# unit-shield.net
KiCad netlist of a schematic drawn in EAGLE
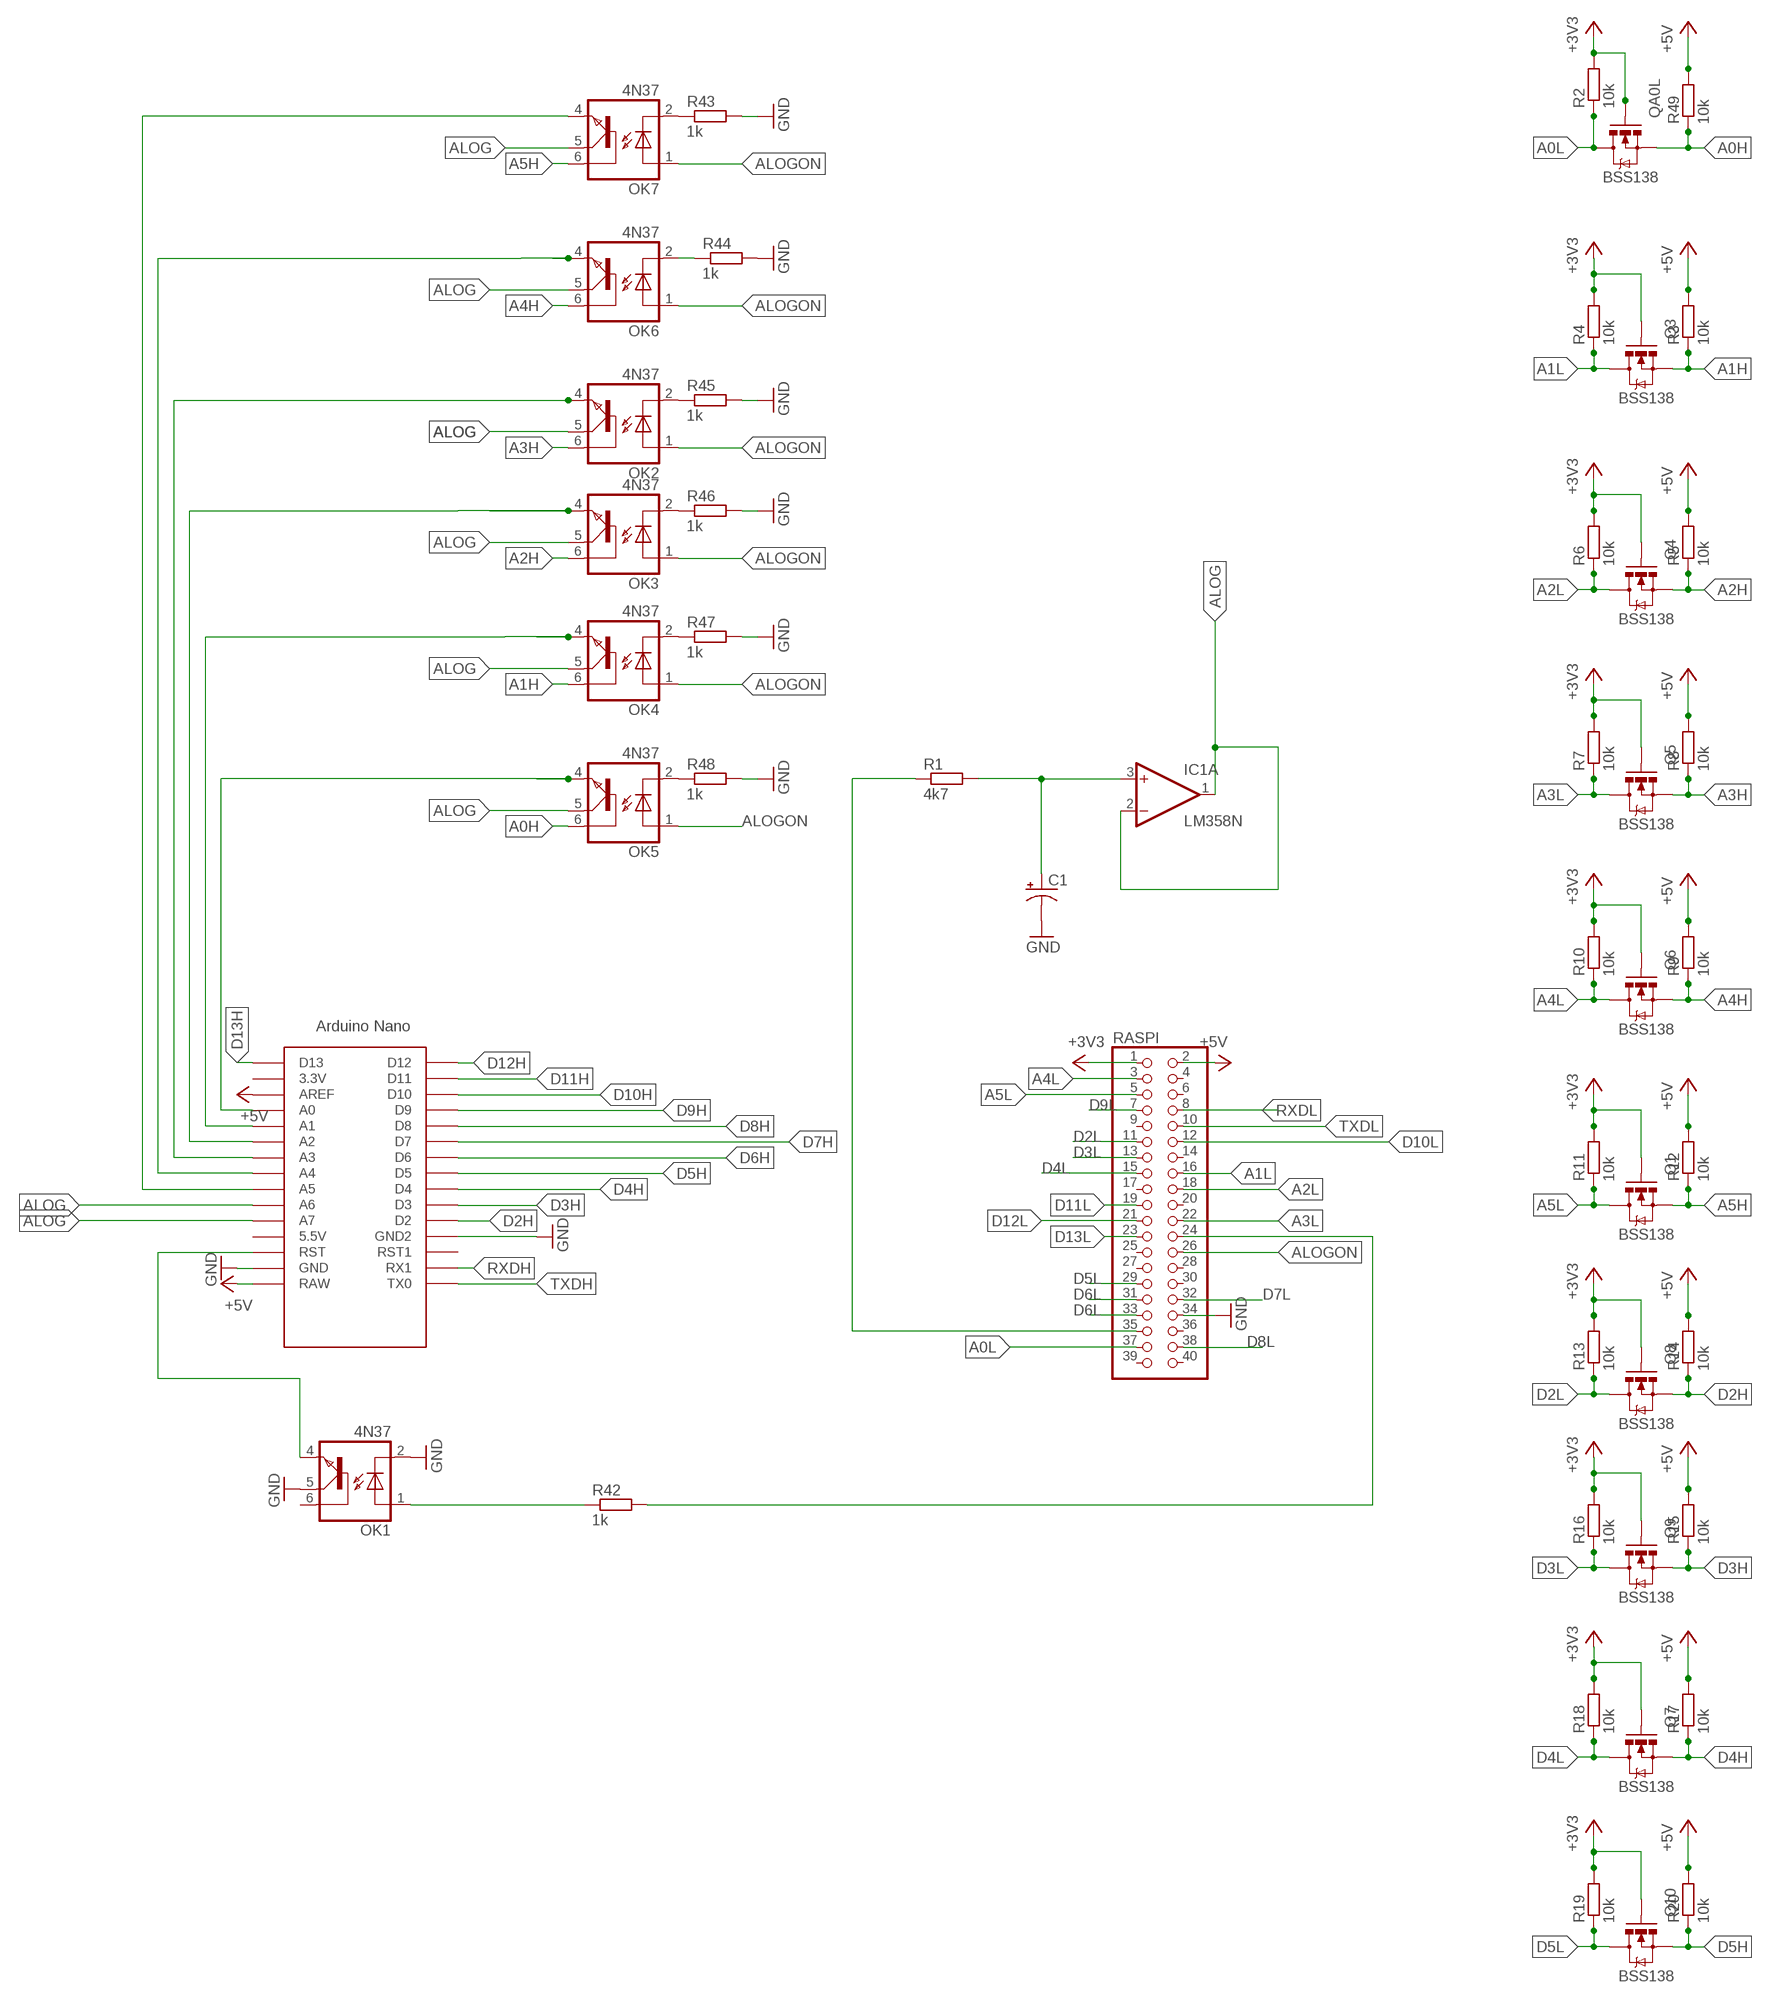
[diagram p0: schematic, sheet 1, part 1 of 2]
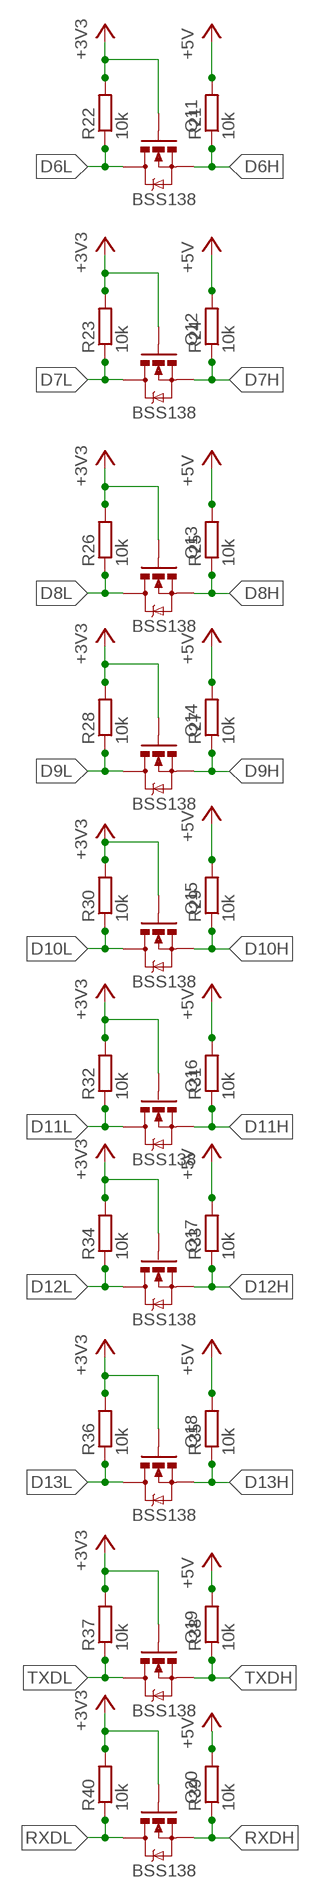
[diagram p1: schematic, sheet 1, part 2 of 2]

(export (version "E")
  (design (tool "Eeschema 10.0.6"))
  (components
    (comp (ref "C1")
      (value "CPOL-USB")
      (footprint "eagle-import:PANASONIC_B")
      (libsource (lib "eagle-import") (part "CPOL-USB"))
    )
    (comp (ref "IC1")
      (value "LM358N")
      (footprint "eagle-import:DIL08")
      (libsource (lib "eagle-import") (part "LM358N"))
    )
    (comp (ref "OK1")
      (value "4N37")
      (footprint "eagle-import:DIL06")
      (fields (field (name "MF") "FAIRCHILD SEMICONDUCTOR"))
      (libsource (lib "eagle-import") (part "4N37"))
    )
    (comp (ref "OK2")
      (value "4N37")
      (footprint "eagle-import:DIL06")
      (fields (field (name "MF") "FAIRCHILD SEMICONDUCTOR"))
      (libsource (lib "eagle-import") (part "4N37"))
    )
    (comp (ref "OK3")
      (value "4N37")
      (footprint "eagle-import:DIL06")
      (fields (field (name "MF") "FAIRCHILD SEMICONDUCTOR"))
      (libsource (lib "eagle-import") (part "4N37"))
    )
    (comp (ref "OK4")
      (value "4N37")
      (footprint "eagle-import:DIL06")
      (fields (field (name "MF") "FAIRCHILD SEMICONDUCTOR"))
      (libsource (lib "eagle-import") (part "4N37"))
    )
    (comp (ref "OK5")
      (value "4N37")
      (footprint "eagle-import:DIL06")
      (fields (field (name "MF") "FAIRCHILD SEMICONDUCTOR"))
      (libsource (lib "eagle-import") (part "4N37"))
    )
    (comp (ref "OK6")
      (value "4N37")
      (footprint "eagle-import:DIL06")
      (fields (field (name "MF") "FAIRCHILD SEMICONDUCTOR"))
      (libsource (lib "eagle-import") (part "4N37"))
    )
    (comp (ref "OK7")
      (value "4N37")
      (footprint "eagle-import:DIL06")
      (fields (field (name "MF") "FAIRCHILD SEMICONDUCTOR"))
      (libsource (lib "eagle-import") (part "4N37"))
    )
    (comp (ref "Q1")
      (value "BSS138")
      (footprint "eagle-import:SOT23-3")
      (libsource (lib "eagle-import") (part "MOSFET-NCHANNELSMD"))
    )
    (comp (ref "Q3")
      (value "BSS138")
      (footprint "eagle-import:SOT23-3")
      (libsource (lib "eagle-import") (part "MOSFET-NCHANNELSMD"))
    )
    (comp (ref "Q4")
      (value "BSS138")
      (footprint "eagle-import:SOT23-3")
      (libsource (lib "eagle-import") (part "MOSFET-NCHANNELSMD"))
    )
    (comp (ref "Q5")
      (value "BSS138")
      (footprint "eagle-import:SOT23-3")
      (libsource (lib "eagle-import") (part "MOSFET-NCHANNELSMD"))
    )
    (comp (ref "Q6")
      (value "BSS138")
      (footprint "eagle-import:SOT23-3")
      (libsource (lib "eagle-import") (part "MOSFET-NCHANNELSMD"))
    )
    (comp (ref "Q7")
      (value "BSS138")
      (footprint "eagle-import:SOT23-3")
      (libsource (lib "eagle-import") (part "MOSFET-NCHANNELSMD"))
    )
    (comp (ref "Q8")
      (value "BSS138")
      (footprint "eagle-import:SOT23-3")
      (libsource (lib "eagle-import") (part "MOSFET-NCHANNELSMD"))
    )
    (comp (ref "Q9")
      (value "BSS138")
      (footprint "eagle-import:SOT23-3")
      (libsource (lib "eagle-import") (part "MOSFET-NCHANNELSMD"))
    )
    (comp (ref "Q10")
      (value "BSS138")
      (footprint "eagle-import:SOT23-3")
      (libsource (lib "eagle-import") (part "MOSFET-NCHANNELSMD"))
    )
    (comp (ref "Q11")
      (value "BSS138")
      (footprint "eagle-import:SOT23-3")
      (libsource (lib "eagle-import") (part "MOSFET-NCHANNELSMD"))
    )
    (comp (ref "Q12")
      (value "BSS138")
      (footprint "eagle-import:SOT23-3")
      (libsource (lib "eagle-import") (part "MOSFET-NCHANNELSMD"))
    )
    (comp (ref "Q13")
      (value "BSS138")
      (footprint "eagle-import:SOT23-3")
      (libsource (lib "eagle-import") (part "MOSFET-NCHANNELSMD"))
    )
    (comp (ref "Q14")
      (value "BSS138")
      (footprint "eagle-import:SOT23-3")
      (libsource (lib "eagle-import") (part "MOSFET-NCHANNELSMD"))
    )
    (comp (ref "Q15")
      (value "BSS138")
      (footprint "eagle-import:SOT23-3")
      (libsource (lib "eagle-import") (part "MOSFET-NCHANNELSMD"))
    )
    (comp (ref "Q16")
      (value "BSS138")
      (footprint "eagle-import:SOT23-3")
      (libsource (lib "eagle-import") (part "MOSFET-NCHANNELSMD"))
    )
    (comp (ref "Q17")
      (value "BSS138")
      (footprint "eagle-import:SOT23-3")
      (libsource (lib "eagle-import") (part "MOSFET-NCHANNELSMD"))
    )
    (comp (ref "Q18")
      (value "BSS138")
      (footprint "eagle-import:SOT23-3")
      (libsource (lib "eagle-import") (part "MOSFET-NCHANNELSMD"))
    )
    (comp (ref "Q19")
      (value "BSS138")
      (footprint "eagle-import:SOT23-3")
      (libsource (lib "eagle-import") (part "MOSFET-NCHANNELSMD"))
    )
    (comp (ref "Q20")
      (value "BSS138")
      (footprint "eagle-import:SOT23-3")
      (libsource (lib "eagle-import") (part "MOSFET-NCHANNELSMD"))
    )
    (comp (ref "QA0L")
      (value "BSS138")
      (footprint "eagle-import:SOT23-3")
      (libsource (lib "eagle-import") (part "MOSFET-NCHANNELSMD"))
    )
    (comp (ref "R1")
      (value "4k7")
      (footprint "eagle-import:M3216")
      (libsource (lib "eagle-import") (part "R-EU_M3216"))
    )
    (comp (ref "R2")
      (value "10k")
      (footprint "eagle-import:M3216")
      (libsource (lib "eagle-import") (part "R-EU_M3216"))
    )
    (comp (ref "R3")
      (value "10k")
      (footprint "eagle-import:M3216")
      (libsource (lib "eagle-import") (part "R-EU_M3216"))
    )
    (comp (ref "R4")
      (value "10k")
      (footprint "eagle-import:M3216")
      (libsource (lib "eagle-import") (part "R-EU_M3216"))
    )
    (comp (ref "R5")
      (value "10k")
      (footprint "eagle-import:M3216")
      (libsource (lib "eagle-import") (part "R-EU_M3216"))
    )
    (comp (ref "R6")
      (value "10k")
      (footprint "eagle-import:M3216")
      (libsource (lib "eagle-import") (part "R-EU_M3216"))
    )
    (comp (ref "R7")
      (value "10k")
      (footprint "eagle-import:M3216")
      (libsource (lib "eagle-import") (part "R-EU_M3216"))
    )
    (comp (ref "R8")
      (value "10k")
      (footprint "eagle-import:M3216")
      (libsource (lib "eagle-import") (part "R-EU_M3216"))
    )
    (comp (ref "R9")
      (value "10k")
      (footprint "eagle-import:M3216")
      (libsource (lib "eagle-import") (part "R-EU_M3216"))
    )
    (comp (ref "R10")
      (value "10k")
      (footprint "eagle-import:M3216")
      (libsource (lib "eagle-import") (part "R-EU_M3216"))
    )
    (comp (ref "R11")
      (value "10k")
      (footprint "eagle-import:M3216")
      (libsource (lib "eagle-import") (part "R-EU_M3216"))
    )
    (comp (ref "R12")
      (value "10k")
      (footprint "eagle-import:M3216")
      (libsource (lib "eagle-import") (part "R-EU_M3216"))
    )
    (comp (ref "R13")
      (value "10k")
      (footprint "eagle-import:M3216")
      (libsource (lib "eagle-import") (part "R-EU_M3216"))
    )
    (comp (ref "R14")
      (value "10k")
      (footprint "eagle-import:M3216")
      (libsource (lib "eagle-import") (part "R-EU_M3216"))
    )
    (comp (ref "R15")
      (value "10k")
      (footprint "eagle-import:M3216")
      (libsource (lib "eagle-import") (part "R-EU_M3216"))
    )
    (comp (ref "R16")
      (value "10k")
      (footprint "eagle-import:M3216")
      (libsource (lib "eagle-import") (part "R-EU_M3216"))
    )
    (comp (ref "R17")
      (value "10k")
      (footprint "eagle-import:M3216")
      (libsource (lib "eagle-import") (part "R-EU_M3216"))
    )
    (comp (ref "R18")
      (value "10k")
      (footprint "eagle-import:M3216")
      (libsource (lib "eagle-import") (part "R-EU_M3216"))
    )
    (comp (ref "R19")
      (value "10k")
      (footprint "eagle-import:M3216")
      (libsource (lib "eagle-import") (part "R-EU_M3216"))
    )
    (comp (ref "R20")
      (value "10k")
      (footprint "eagle-import:M3216")
      (libsource (lib "eagle-import") (part "R-EU_M3216"))
    )
    (comp (ref "R21")
      (value "10k")
      (footprint "eagle-import:M3216")
      (libsource (lib "eagle-import") (part "R-EU_M3216"))
    )
    (comp (ref "R22")
      (value "10k")
      (footprint "eagle-import:M3216")
      (libsource (lib "eagle-import") (part "R-EU_M3216"))
    )
    (comp (ref "R23")
      (value "10k")
      (footprint "eagle-import:M3216")
      (libsource (lib "eagle-import") (part "R-EU_M3216"))
    )
    (comp (ref "R24")
      (value "10k")
      (footprint "eagle-import:M3216")
      (libsource (lib "eagle-import") (part "R-EU_M3216"))
    )
    (comp (ref "R25")
      (value "10k")
      (footprint "eagle-import:M3216")
      (libsource (lib "eagle-import") (part "R-EU_M3216"))
    )
    (comp (ref "R26")
      (value "10k")
      (footprint "eagle-import:M3216")
      (libsource (lib "eagle-import") (part "R-EU_M3216"))
    )
    (comp (ref "R27")
      (value "10k")
      (footprint "eagle-import:M3216")
      (libsource (lib "eagle-import") (part "R-EU_M3216"))
    )
    (comp (ref "R28")
      (value "10k")
      (footprint "eagle-import:M3216")
      (libsource (lib "eagle-import") (part "R-EU_M3216"))
    )
    (comp (ref "R29")
      (value "10k")
      (footprint "eagle-import:M3216")
      (libsource (lib "eagle-import") (part "R-EU_M3216"))
    )
    (comp (ref "R30")
      (value "10k")
      (footprint "eagle-import:M3216")
      (libsource (lib "eagle-import") (part "R-EU_M3216"))
    )
    (comp (ref "R31")
      (value "10k")
      (footprint "eagle-import:M3216")
      (libsource (lib "eagle-import") (part "R-EU_M3216"))
    )
    (comp (ref "R32")
      (value "10k")
      (footprint "eagle-import:M3216")
      (libsource (lib "eagle-import") (part "R-EU_M3216"))
    )
    (comp (ref "R33")
      (value "10k")
      (footprint "eagle-import:M3216")
      (libsource (lib "eagle-import") (part "R-EU_M3216"))
    )
    (comp (ref "R34")
      (value "10k")
      (footprint "eagle-import:M3216")
      (libsource (lib "eagle-import") (part "R-EU_M3216"))
    )
    (comp (ref "R35")
      (value "10k")
      (footprint "eagle-import:M3216")
      (libsource (lib "eagle-import") (part "R-EU_M3216"))
    )
    (comp (ref "R36")
      (value "10k")
      (footprint "eagle-import:M3216")
      (libsource (lib "eagle-import") (part "R-EU_M3216"))
    )
    (comp (ref "R37")
      (value "10k")
      (footprint "eagle-import:M3216")
      (libsource (lib "eagle-import") (part "R-EU_M3216"))
    )
    (comp (ref "R38")
      (value "10k")
      (footprint "eagle-import:M3216")
      (libsource (lib "eagle-import") (part "R-EU_M3216"))
    )
    (comp (ref "R39")
      (value "10k")
      (footprint "eagle-import:M3216")
      (libsource (lib "eagle-import") (part "R-EU_M3216"))
    )
    (comp (ref "R40")
      (value "10k")
      (footprint "eagle-import:M3216")
      (libsource (lib "eagle-import") (part "R-EU_M3216"))
    )
    (comp (ref "R42")
      (value "1k")
      (footprint "eagle-import:M3216")
      (libsource (lib "eagle-import") (part "R-EU_M3216"))
    )
    (comp (ref "R43")
      (value "1k")
      (footprint "eagle-import:M3216")
      (libsource (lib "eagle-import") (part "R-EU_M3216"))
    )
    (comp (ref "R44")
      (value "1k")
      (footprint "eagle-import:M3216")
      (libsource (lib "eagle-import") (part "R-EU_M3216"))
    )
    (comp (ref "R45")
      (value "1k")
      (footprint "eagle-import:M3216")
      (libsource (lib "eagle-import") (part "R-EU_M3216"))
    )
    (comp (ref "R46")
      (value "1k")
      (footprint "eagle-import:M3216")
      (libsource (lib "eagle-import") (part "R-EU_M3216"))
    )
    (comp (ref "R47")
      (value "1k")
      (footprint "eagle-import:M3216")
      (libsource (lib "eagle-import") (part "R-EU_M3216"))
    )
    (comp (ref "R48")
      (value "1k")
      (footprint "eagle-import:M3216")
      (libsource (lib "eagle-import") (part "R-EU_M3216"))
    )
    (comp (ref "R49")
      (value "10k")
      (footprint "eagle-import:M3216")
      (libsource (lib "eagle-import") (part "R-EU_M3216"))
    )
    (comp (ref "RASPI")
      (value "PINHD-2X20")
      (footprint "eagle-import:2X20")
      (libsource (lib "eagle-import") (part "PINHD-2X20"))
    )
    (comp (ref "U$1")
      (value "NANO")
      (footprint "eagle-import:NANO")
      (libsource (lib "eagle-import") (part "NANO"))
    )
  )
  (nets
    (net (code "1") (name "+3V3") (class "Default")
      (node (ref "Q1") (pin "1") (pinfunction "G_1") (pintype "passive"))
      (node (ref "Q10") (pin "1") (pinfunction "G_1") (pintype "passive"))
      (node (ref "Q11") (pin "1") (pinfunction "G_1") (pintype "passive"))
      (node (ref "Q12") (pin "1") (pinfunction "G_1") (pintype "passive"))
      (node (ref "Q13") (pin "1") (pinfunction "G_1") (pintype "passive"))
      (node (ref "Q14") (pin "1") (pinfunction "G_1") (pintype "passive"))
      (node (ref "Q15") (pin "1") (pinfunction "G_1") (pintype "passive"))
      (node (ref "Q16") (pin "1") (pinfunction "G_1") (pintype "passive"))
      (node (ref "Q17") (pin "1") (pinfunction "G_1") (pintype "passive"))
      (node (ref "Q18") (pin "1") (pinfunction "G_1") (pintype "passive"))
      (node (ref "Q19") (pin "1") (pinfunction "G_1") (pintype "passive"))
      (node (ref "Q20") (pin "1") (pinfunction "G_1") (pintype "passive"))
      (node (ref "Q3") (pin "1") (pinfunction "G_1") (pintype "passive"))
      (node (ref "Q4") (pin "1") (pinfunction "G_1") (pintype "passive"))
      (node (ref "Q5") (pin "1") (pinfunction "G_1") (pintype "passive"))
      (node (ref "Q6") (pin "1") (pinfunction "G_1") (pintype "passive"))
      (node (ref "Q7") (pin "1") (pinfunction "G_1") (pintype "passive"))
      (node (ref "Q8") (pin "1") (pinfunction "G_1") (pintype "passive"))
      (node (ref "Q9") (pin "1") (pinfunction "G_1") (pintype "passive"))
      (node (ref "QA0L") (pin "1") (pinfunction "G_1") (pintype "passive"))
      (node (ref "R10") (pin "2") (pinfunction "2_2") (pintype "passive"))
      (node (ref "R11") (pin "2") (pinfunction "2_2") (pintype "passive"))
      (node (ref "R13") (pin "2") (pinfunction "2_2") (pintype "passive"))
      (node (ref "R16") (pin "2") (pinfunction "2_2") (pintype "passive"))
      (node (ref "R18") (pin "2") (pinfunction "2_2") (pintype "passive"))
      (node (ref "R19") (pin "2") (pinfunction "2_2") (pintype "passive"))
      (node (ref "R2") (pin "2") (pinfunction "2_2") (pintype "passive"))
      (node (ref "R22") (pin "2") (pinfunction "2_2") (pintype "passive"))
      (node (ref "R23") (pin "2") (pinfunction "2_2") (pintype "passive"))
      (node (ref "R26") (pin "2") (pinfunction "2_2") (pintype "passive"))
      (node (ref "R28") (pin "2") (pinfunction "2_2") (pintype "passive"))
      (node (ref "R30") (pin "2") (pinfunction "2_2") (pintype "passive"))
      (node (ref "R32") (pin "2") (pinfunction "2_2") (pintype "passive"))
      (node (ref "R34") (pin "2") (pinfunction "2_2") (pintype "passive"))
      (node (ref "R36") (pin "2") (pinfunction "2_2") (pintype "passive"))
      (node (ref "R37") (pin "2") (pinfunction "2_2") (pintype "passive"))
      (node (ref "R4") (pin "2") (pinfunction "2_2") (pintype "passive"))
      (node (ref "R40") (pin "2") (pinfunction "2_2") (pintype "passive"))
      (node (ref "R6") (pin "2") (pinfunction "2_2") (pintype "passive"))
      (node (ref "R7") (pin "2") (pinfunction "2_2") (pintype "passive"))
      (node (ref "RASPI") (pin "1") (pinfunction "1_1") (pintype "passive"))
    )
    (net (code "2") (name "+5V") (class "Default")
      (node (ref "R12") (pin "2") (pinfunction "2_2") (pintype "passive"))
      (node (ref "R14") (pin "2") (pinfunction "2_2") (pintype "passive"))
      (node (ref "R15") (pin "2") (pinfunction "2_2") (pintype "passive"))
      (node (ref "R17") (pin "2") (pinfunction "2_2") (pintype "passive"))
      (node (ref "R20") (pin "2") (pinfunction "2_2") (pintype "passive"))
      (node (ref "R21") (pin "2") (pinfunction "2_2") (pintype "passive"))
      (node (ref "R24") (pin "2") (pinfunction "2_2") (pintype "passive"))
      (node (ref "R25") (pin "2") (pinfunction "2_2") (pintype "passive"))
      (node (ref "R27") (pin "2") (pinfunction "2_2") (pintype "passive"))
      (node (ref "R29") (pin "2") (pinfunction "2_2") (pintype "passive"))
      (node (ref "R3") (pin "2") (pinfunction "2_2") (pintype "passive"))
      (node (ref "R31") (pin "2") (pinfunction "2_2") (pintype "passive"))
      (node (ref "R33") (pin "2") (pinfunction "2_2") (pintype "passive"))
      (node (ref "R35") (pin "2") (pinfunction "2_2") (pintype "passive"))
      (node (ref "R38") (pin "2") (pinfunction "2_2") (pintype "passive"))
      (node (ref "R39") (pin "2") (pinfunction "2_2") (pintype "passive"))
      (node (ref "R49") (pin "2") (pinfunction "2_2") (pintype "passive"))
      (node (ref "R5") (pin "2") (pinfunction "2_2") (pintype "passive"))
      (node (ref "R8") (pin "2") (pinfunction "2_2") (pintype "passive"))
      (node (ref "R9") (pin "2") (pinfunction "2_2") (pintype "passive"))
      (node (ref "RASPI") (pin "2") (pinfunction "2_2") (pintype "passive"))
      (node (ref "U$1") (pin "AREF") (pinfunction "AREF_AREF") (pintype "bidirectional"))
      (node (ref "U$1") (pin "RAW") (pinfunction "RAW_RAW") (pintype "bidirectional"))
    )
    (net (code "3") (name "A0H") (class "Default")
      (node (ref "OK5") (pin "6") (pinfunction "BAS_6") (pintype "passive"))
      (node (ref "QA0L") (pin "2") (pinfunction "S_2") (pintype "passive"))
      (node (ref "R49") (pin "1") (pinfunction "1_1") (pintype "passive"))
    )
    (net (code "4") (name "A0L") (class "Default")
      (node (ref "QA0L") (pin "3") (pinfunction "D_3") (pintype "passive"))
      (node (ref "R2") (pin "1") (pinfunction "1_1") (pintype "passive"))
      (node (ref "RASPI") (pin "37") (pinfunction "37_37") (pintype "passive"))
    )
    (net (code "5") (name "A1H") (class "Default")
      (node (ref "OK4") (pin "6") (pinfunction "BAS_6") (pintype "passive"))
      (node (ref "Q3") (pin "2") (pinfunction "S_2") (pintype "passive"))
      (node (ref "R3") (pin "1") (pinfunction "1_1") (pintype "passive"))
    )
    (net (code "6") (name "A1L") (class "Default")
      (node (ref "Q3") (pin "3") (pinfunction "D_3") (pintype "passive"))
      (node (ref "R4") (pin "1") (pinfunction "1_1") (pintype "passive"))
      (node (ref "RASPI") (pin "16") (pinfunction "16_16") (pintype "passive"))
    )
    (net (code "7") (name "A2H") (class "Default")
      (node (ref "OK3") (pin "6") (pinfunction "BAS_6") (pintype "passive"))
      (node (ref "Q4") (pin "2") (pinfunction "S_2") (pintype "passive"))
      (node (ref "R5") (pin "1") (pinfunction "1_1") (pintype "passive"))
    )
    (net (code "8") (name "A2L") (class "Default")
      (node (ref "Q4") (pin "3") (pinfunction "D_3") (pintype "passive"))
      (node (ref "R6") (pin "1") (pinfunction "1_1") (pintype "passive"))
      (node (ref "RASPI") (pin "18") (pinfunction "18_18") (pintype "passive"))
    )
    (net (code "9") (name "A3H") (class "Default")
      (node (ref "OK2") (pin "6") (pinfunction "BAS_6") (pintype "passive"))
      (node (ref "Q5") (pin "2") (pinfunction "S_2") (pintype "passive"))
      (node (ref "R8") (pin "1") (pinfunction "1_1") (pintype "passive"))
    )
    (net (code "10") (name "A3L") (class "Default")
      (node (ref "Q5") (pin "3") (pinfunction "D_3") (pintype "passive"))
      (node (ref "R7") (pin "1") (pinfunction "1_1") (pintype "passive"))
      (node (ref "RASPI") (pin "22") (pinfunction "22_22") (pintype "passive"))
    )
    (net (code "11") (name "A4H") (class "Default")
      (node (ref "OK6") (pin "6") (pinfunction "BAS_6") (pintype "passive"))
      (node (ref "Q6") (pin "2") (pinfunction "S_2") (pintype "passive"))
      (node (ref "R9") (pin "1") (pinfunction "1_1") (pintype "passive"))
    )
    (net (code "12") (name "A4L") (class "Default")
      (node (ref "Q6") (pin "3") (pinfunction "D_3") (pintype "passive"))
      (node (ref "R10") (pin "1") (pinfunction "1_1") (pintype "passive"))
      (node (ref "RASPI") (pin "3") (pinfunction "3_3") (pintype "passive"))
    )
    (net (code "13") (name "A5H") (class "Default")
      (node (ref "OK7") (pin "6") (pinfunction "BAS_6") (pintype "passive"))
      (node (ref "Q1") (pin "2") (pinfunction "S_2") (pintype "passive"))
      (node (ref "R12") (pin "1") (pinfunction "1_1") (pintype "passive"))
    )
    (net (code "14") (name "A5L") (class "Default")
      (node (ref "Q1") (pin "3") (pinfunction "D_3") (pintype "passive"))
      (node (ref "R11") (pin "1") (pinfunction "1_1") (pintype "passive"))
      (node (ref "RASPI") (pin "5") (pinfunction "5_5") (pintype "passive"))
    )
    (net (code "15") (name "ALOG") (class "Default")
      (node (ref "IC1") (pin "1") (pinfunction "OUT_1") (pintype "output"))
      (node (ref "IC1") (pin "2") (pinfunction "-IN_2") (pintype "input"))
      (node (ref "OK2") (pin "5") (pinfunction "COL_5") (pintype "passive"))
      (node (ref "OK3") (pin "5") (pinfunction "COL_5") (pintype "passive"))
      (node (ref "OK4") (pin "5") (pinfunction "COL_5") (pintype "passive"))
      (node (ref "OK5") (pin "5") (pinfunction "COL_5") (pintype "passive"))
      (node (ref "OK6") (pin "5") (pinfunction "COL_5") (pintype "passive"))
      (node (ref "OK7") (pin "5") (pinfunction "COL_5") (pintype "passive"))
      (node (ref "U$1") (pin "A6") (pinfunction "A6_A6") (pintype "bidirectional"))
      (node (ref "U$1") (pin "A7") (pinfunction "A7_A7") (pintype "bidirectional"))
    )
    (net (code "16") (name "ALOGON") (class "Default")
      (node (ref "OK2") (pin "1") (pinfunction "A_1") (pintype "passive"))
      (node (ref "OK3") (pin "1") (pinfunction "A_1") (pintype "passive"))
      (node (ref "OK4") (pin "1") (pinfunction "A_1") (pintype "passive"))
      (node (ref "OK5") (pin "1") (pinfunction "A_1") (pintype "passive"))
      (node (ref "OK6") (pin "1") (pinfunction "A_1") (pintype "passive"))
      (node (ref "OK7") (pin "1") (pinfunction "A_1") (pintype "passive"))
      (node (ref "RASPI") (pin "26") (pinfunction "26_26") (pintype "passive"))
    )
    (net (code "17") (name "D2H") (class "Default")
      (node (ref "Q8") (pin "2") (pinfunction "S_2") (pintype "passive"))
      (node (ref "R14") (pin "1") (pinfunction "1_1") (pintype "passive"))
      (node (ref "U$1") (pin "D2") (pinfunction "D2_D2") (pintype "bidirectional"))
    )
    (net (code "18") (name "D2L") (class "Default")
      (node (ref "Q8") (pin "3") (pinfunction "D_3") (pintype "passive"))
      (node (ref "R13") (pin "1") (pinfunction "1_1") (pintype "passive"))
      (node (ref "RASPI") (pin "11") (pinfunction "11_11") (pintype "passive"))
    )
    (net (code "19") (name "D3H") (class "Default")
      (node (ref "Q9") (pin "2") (pinfunction "S_2") (pintype "passive"))
      (node (ref "R15") (pin "1") (pinfunction "1_1") (pintype "passive"))
      (node (ref "U$1") (pin "D3") (pinfunction "D3_D3") (pintype "bidirectional"))
    )
    (net (code "20") (name "D3L") (class "Default")
      (node (ref "Q9") (pin "3") (pinfunction "D_3") (pintype "passive"))
      (node (ref "R16") (pin "1") (pinfunction "1_1") (pintype "passive"))
      (node (ref "RASPI") (pin "13") (pinfunction "13_13") (pintype "passive"))
    )
    (net (code "21") (name "D4H") (class "Default")
      (node (ref "Q7") (pin "2") (pinfunction "S_2") (pintype "passive"))
      (node (ref "R17") (pin "1") (pinfunction "1_1") (pintype "passive"))
      (node (ref "U$1") (pin "D4") (pinfunction "D4_D4") (pintype "bidirectional"))
    )
    (net (code "22") (name "D4L") (class "Default")
      (node (ref "Q7") (pin "3") (pinfunction "D_3") (pintype "passive"))
      (node (ref "R18") (pin "1") (pinfunction "1_1") (pintype "passive"))
      (node (ref "RASPI") (pin "15") (pinfunction "15_15") (pintype "passive"))
    )
    (net (code "23") (name "D5H") (class "Default")
      (node (ref "Q10") (pin "2") (pinfunction "S_2") (pintype "passive"))
      (node (ref "R20") (pin "1") (pinfunction "1_1") (pintype "passive"))
      (node (ref "U$1") (pin "D5") (pinfunction "D5_D5") (pintype "bidirectional"))
    )
    (net (code "24") (name "D5L") (class "Default")
      (node (ref "Q10") (pin "3") (pinfunction "D_3") (pintype "passive"))
      (node (ref "R19") (pin "1") (pinfunction "1_1") (pintype "passive"))
      (node (ref "RASPI") (pin "29") (pinfunction "29_29") (pintype "passive"))
    )
    (net (code "25") (name "D6H") (class "Default")
      (node (ref "Q11") (pin "2") (pinfunction "S_2") (pintype "passive"))
      (node (ref "R21") (pin "1") (pinfunction "1_1") (pintype "passive"))
      (node (ref "U$1") (pin "D6") (pinfunction "D6_D6") (pintype "bidirectional"))
    )
    (net (code "26") (name "D6L") (class "Default")
      (node (ref "Q11") (pin "3") (pinfunction "D_3") (pintype "passive"))
      (node (ref "R22") (pin "1") (pinfunction "1_1") (pintype "passive"))
      (node (ref "RASPI") (pin "31") (pinfunction "31_31") (pintype "passive"))
      (node (ref "RASPI") (pin "33") (pinfunction "33_33") (pintype "passive"))
    )
    (net (code "27") (name "D7H") (class "Default")
      (node (ref "Q12") (pin "2") (pinfunction "S_2") (pintype "passive"))
      (node (ref "R24") (pin "1") (pinfunction "1_1") (pintype "passive"))
      (node (ref "U$1") (pin "D7") (pinfunction "D7_D7") (pintype "bidirectional"))
    )
    (net (code "28") (name "D7L") (class "Default")
      (node (ref "Q12") (pin "3") (pinfunction "D_3") (pintype "passive"))
      (node (ref "R23") (pin "1") (pinfunction "1_1") (pintype "passive"))
      (node (ref "RASPI") (pin "32") (pinfunction "32_32") (pintype "passive"))
    )
    (net (code "29") (name "D8H") (class "Default")
      (node (ref "Q13") (pin "2") (pinfunction "S_2") (pintype "passive"))
      (node (ref "R25") (pin "1") (pinfunction "1_1") (pintype "passive"))
      (node (ref "U$1") (pin "D8") (pinfunction "D8_D8") (pintype "bidirectional"))
    )
    (net (code "30") (name "D8L") (class "Default")
      (node (ref "Q13") (pin "3") (pinfunction "D_3") (pintype "passive"))
      (node (ref "R26") (pin "1") (pinfunction "1_1") (pintype "passive"))
      (node (ref "RASPI") (pin "38") (pinfunction "38_38") (pintype "passive"))
    )
    (net (code "31") (name "D9H") (class "Default")
      (node (ref "Q14") (pin "2") (pinfunction "S_2") (pintype "passive"))
      (node (ref "R27") (pin "1") (pinfunction "1_1") (pintype "passive"))
      (node (ref "U$1") (pin "D9") (pinfunction "D9_D9") (pintype "bidirectional"))
    )
    (net (code "32") (name "D9L") (class "Default")
      (node (ref "Q14") (pin "3") (pinfunction "D_3") (pintype "passive"))
      (node (ref "R28") (pin "1") (pinfunction "1_1") (pintype "passive"))
      (node (ref "RASPI") (pin "7") (pinfunction "7_7") (pintype "passive"))
    )
    (net (code "33") (name "D10H") (class "Default")
      (node (ref "Q15") (pin "2") (pinfunction "S_2") (pintype "passive"))
      (node (ref "R29") (pin "1") (pinfunction "1_1") (pintype "passive"))
      (node (ref "U$1") (pin "D10") (pinfunction "D10_D10") (pintype "bidirectional"))
    )
    (net (code "34") (name "D10L") (class "Default")
      (node (ref "Q15") (pin "3") (pinfunction "D_3") (pintype "passive"))
      (node (ref "R30") (pin "1") (pinfunction "1_1") (pintype "passive"))
      (node (ref "RASPI") (pin "12") (pinfunction "12_12") (pintype "passive"))
    )
    (net (code "35") (name "D11H") (class "Default")
      (node (ref "Q16") (pin "2") (pinfunction "S_2") (pintype "passive"))
      (node (ref "R31") (pin "1") (pinfunction "1_1") (pintype "passive"))
      (node (ref "U$1") (pin "D11") (pinfunction "D11_D11") (pintype "bidirectional"))
    )
    (net (code "36") (name "D11L") (class "Default")
      (node (ref "Q16") (pin "3") (pinfunction "D_3") (pintype "passive"))
      (node (ref "R32") (pin "1") (pinfunction "1_1") (pintype "passive"))
      (node (ref "RASPI") (pin "19") (pinfunction "19_19") (pintype "passive"))
    )
    (net (code "37") (name "D12H") (class "Default")
      (node (ref "Q17") (pin "2") (pinfunction "S_2") (pintype "passive"))
      (node (ref "R33") (pin "1") (pinfunction "1_1") (pintype "passive"))
      (node (ref "U$1") (pin "D12") (pinfunction "D12_D12") (pintype "bidirectional"))
    )
    (net (code "38") (name "D12L") (class "Default")
      (node (ref "Q17") (pin "3") (pinfunction "D_3") (pintype "passive"))
      (node (ref "R34") (pin "1") (pinfunction "1_1") (pintype "passive"))
      (node (ref "RASPI") (pin "21") (pinfunction "21_21") (pintype "passive"))
    )
    (net (code "39") (name "D13H") (class "Default")
      (node (ref "Q18") (pin "2") (pinfunction "S_2") (pintype "passive"))
      (node (ref "R35") (pin "1") (pinfunction "1_1") (pintype "passive"))
      (node (ref "U$1") (pin "D13") (pinfunction "D13_D13") (pintype "bidirectional"))
    )
    (net (code "40") (name "D13L") (class "Default")
      (node (ref "Q18") (pin "3") (pinfunction "D_3") (pintype "passive"))
      (node (ref "R36") (pin "1") (pinfunction "1_1") (pintype "passive"))
      (node (ref "RASPI") (pin "23") (pinfunction "23_23") (pintype "passive"))
    )
    (net (code "41") (name "GND") (class "Default")
      (node (ref "C1") (pin "-") (pinfunction "-_-") (pintype "passive"))
      (node (ref "OK1") (pin "2") (pinfunction "C_2") (pintype "passive"))
      (node (ref "OK1") (pin "5") (pinfunction "COL_5") (pintype "passive"))
      (node (ref "R43") (pin "2") (pinfunction "2_2") (pintype "passive"))
      (node (ref "R44") (pin "2") (pinfunction "2_2") (pintype "passive"))
      (node (ref "R45") (pin "2") (pinfunction "2_2") (pintype "passive"))
      (node (ref "R46") (pin "2") (pinfunction "2_2") (pintype "passive"))
      (node (ref "R47") (pin "2") (pinfunction "2_2") (pintype "passive"))
      (node (ref "R48") (pin "2") (pinfunction "2_2") (pintype "passive"))
      (node (ref "RASPI") (pin "34") (pinfunction "34_34") (pintype "passive"))
      (node (ref "U$1") (pin "GND") (pinfunction "GND_GND") (pintype "bidirectional"))
      (node (ref "U$1") (pin "GND1") (pinfunction "GND2_GND1") (pintype "bidirectional"))
    )
    (net (code "42") (name "Net-(IC1A-+IN)") (class "Default")
      (node (ref "C1") (pin "+") (pinfunction "+_+") (pintype "passive"))
      (node (ref "IC1") (pin "3") (pinfunction "+IN_3") (pintype "input"))
      (node (ref "R1") (pin "2") (pinfunction "2_2") (pintype "passive"))
    )
    (net (code "43") (name "Net-(OK1-A)") (class "Default")
      (node (ref "OK1") (pin "1") (pinfunction "A_1") (pintype "passive"))
      (node (ref "R42") (pin "1") (pinfunction "1_1") (pintype "passive"))
    )
    (net (code "44") (name "Net-(OK1-EMI)") (class "Default")
      (node (ref "OK1") (pin "4") (pinfunction "EMI_4") (pintype "passive"))
      (node (ref "U$1") (pin "RST") (pinfunction "RST_RST") (pintype "bidirectional"))
    )
    (net (code "45") (name "Net-(OK2-C)") (class "Default")
      (node (ref "OK2") (pin "2") (pinfunction "C_2") (pintype "passive"))
      (node (ref "R45") (pin "1") (pinfunction "1_1") (pintype "passive"))
    )
    (net (code "46") (name "Net-(OK2-EMI)") (class "Default")
      (node (ref "OK2") (pin "4") (pinfunction "EMI_4") (pintype "passive"))
      (node (ref "U$1") (pin "A3") (pinfunction "A3_A3") (pintype "bidirectional"))
    )
    (net (code "47") (name "Net-(OK3-C)") (class "Default")
      (node (ref "OK3") (pin "2") (pinfunction "C_2") (pintype "passive"))
      (node (ref "R46") (pin "1") (pinfunction "1_1") (pintype "passive"))
    )
    (net (code "48") (name "Net-(OK3-EMI)") (class "Default")
      (node (ref "OK3") (pin "4") (pinfunction "EMI_4") (pintype "passive"))
      (node (ref "U$1") (pin "A2") (pinfunction "A2_A2") (pintype "bidirectional"))
    )
    (net (code "49") (name "Net-(OK4-C)") (class "Default")
      (node (ref "OK4") (pin "2") (pinfunction "C_2") (pintype "passive"))
      (node (ref "R47") (pin "1") (pinfunction "1_1") (pintype "passive"))
    )
    (net (code "50") (name "Net-(OK4-EMI)") (class "Default")
      (node (ref "OK4") (pin "4") (pinfunction "EMI_4") (pintype "passive"))
      (node (ref "U$1") (pin "A1") (pinfunction "A1_A1") (pintype "bidirectional"))
    )
    (net (code "51") (name "Net-(OK5-C)") (class "Default")
      (node (ref "OK5") (pin "2") (pinfunction "C_2") (pintype "passive"))
      (node (ref "R48") (pin "1") (pinfunction "1_1") (pintype "passive"))
    )
    (net (code "52") (name "Net-(OK5-EMI)") (class "Default")
      (node (ref "OK5") (pin "4") (pinfunction "EMI_4") (pintype "passive"))
      (node (ref "U$1") (pin "A0") (pinfunction "A0_A0") (pintype "bidirectional"))
    )
    (net (code "53") (name "Net-(OK6-C)") (class "Default")
      (node (ref "OK6") (pin "2") (pinfunction "C_2") (pintype "passive"))
      (node (ref "R44") (pin "1") (pinfunction "1_1") (pintype "passive"))
    )
    (net (code "54") (name "Net-(OK6-EMI)") (class "Default")
      (node (ref "OK6") (pin "4") (pinfunction "EMI_4") (pintype "passive"))
      (node (ref "U$1") (pin "A4") (pinfunction "A4_A4") (pintype "bidirectional"))
    )
    (net (code "55") (name "Net-(OK7-C)") (class "Default")
      (node (ref "OK7") (pin "2") (pinfunction "C_2") (pintype "passive"))
      (node (ref "R43") (pin "1") (pinfunction "1_1") (pintype "passive"))
    )
    (net (code "56") (name "Net-(OK7-EMI)") (class "Default")
      (node (ref "OK7") (pin "4") (pinfunction "EMI_4") (pintype "passive"))
      (node (ref "U$1") (pin "A5") (pinfunction "A5_A5") (pintype "bidirectional"))
    )
    (net (code "57") (name "Net-(R1-Pad1)") (class "Default")
      (node (ref "R1") (pin "1") (pinfunction "1_1") (pintype "passive"))
      (node (ref "RASPI") (pin "35") (pinfunction "35_35") (pintype "passive"))
    )
    (net (code "58") (name "Net-(R42-Pad2)") (class "Default")
      (node (ref "R42") (pin "2") (pinfunction "2_2") (pintype "passive"))
      (node (ref "RASPI") (pin "24") (pinfunction "24_24") (pintype "passive"))
    )
    (net (code "59") (name "RXDH") (class "Default")
      (node (ref "Q20") (pin "2") (pinfunction "S_2") (pintype "passive"))
      (node (ref "R39") (pin "1") (pinfunction "1_1") (pintype "passive"))
      (node (ref "U$1") (pin "RX1") (pinfunction "RX1_RX1") (pintype "bidirectional"))
    )
    (net (code "60") (name "RXDL") (class "Default")
      (node (ref "Q20") (pin "3") (pinfunction "D_3") (pintype "passive"))
      (node (ref "R40") (pin "1") (pinfunction "1_1") (pintype "passive"))
      (node (ref "RASPI") (pin "8") (pinfunction "8_8") (pintype "passive"))
    )
    (net (code "61") (name "TXDH") (class "Default")
      (node (ref "Q19") (pin "2") (pinfunction "S_2") (pintype "passive"))
      (node (ref "R38") (pin "1") (pinfunction "1_1") (pintype "passive"))
      (node (ref "U$1") (pin "TX0") (pinfunction "TX0_TX0") (pintype "bidirectional"))
    )
    (net (code "62") (name "TXDL") (class "Default")
      (node (ref "Q19") (pin "3") (pinfunction "D_3") (pintype "passive"))
      (node (ref "R37") (pin "1") (pinfunction "1_1") (pintype "passive"))
      (node (ref "RASPI") (pin "10") (pinfunction "10_10") (pintype "passive"))
    )
    (net (code "63") (name "unconnected-(OK1-BAS-Pad6)") (class "Default")
      (node (ref "OK1") (pin "6") (pinfunction "BAS_6") (pintype "passive"))
    )
    (net (code "64") (name "unconnected-(RASPI-Pad4)") (class "Default")
      (node (ref "RASPI") (pin "4") (pinfunction "4_4") (pintype "passive"))
    )
    (net (code "65") (name "unconnected-(RASPI-Pad6)") (class "Default")
      (node (ref "RASPI") (pin "6") (pinfunction "6_6") (pintype "passive"))
    )
    (net (code "66") (name "unconnected-(RASPI-Pad9)") (class "Default")
      (node (ref "RASPI") (pin "9") (pinfunction "9_9") (pintype "passive"))
    )
    (net (code "67") (name "unconnected-(RASPI-Pad14)") (class "Default")
      (node (ref "RASPI") (pin "14") (pinfunction "14_14") (pintype "passive"))
    )
    (net (code "68") (name "unconnected-(RASPI-Pad17)") (class "Default")
      (node (ref "RASPI") (pin "17") (pinfunction "17_17") (pintype "passive"))
    )
    (net (code "69") (name "unconnected-(RASPI-Pad20)") (class "Default")
      (node (ref "RASPI") (pin "20") (pinfunction "20_20") (pintype "passive"))
    )
    (net (code "70") (name "unconnected-(RASPI-Pad25)") (class "Default")
      (node (ref "RASPI") (pin "25") (pinfunction "25_25") (pintype "passive"))
    )
    (net (code "71") (name "unconnected-(RASPI-Pad27)") (class "Default")
      (node (ref "RASPI") (pin "27") (pinfunction "27_27") (pintype "passive"))
    )
    (net (code "72") (name "unconnected-(RASPI-Pad28)") (class "Default")
      (node (ref "RASPI") (pin "28") (pinfunction "28_28") (pintype "passive"))
    )
    (net (code "73") (name "unconnected-(RASPI-Pad30)") (class "Default")
      (node (ref "RASPI") (pin "30") (pinfunction "30_30") (pintype "passive"))
    )
    (net (code "74") (name "unconnected-(RASPI-Pad36)") (class "Default")
      (node (ref "RASPI") (pin "36") (pinfunction "36_36") (pintype "passive"))
    )
    (net (code "75") (name "unconnected-(RASPI-Pad39)") (class "Default")
      (node (ref "RASPI") (pin "39") (pinfunction "39_39") (pintype "passive"))
    )
    (net (code "76") (name "unconnected-(RASPI-Pad40)") (class "Default")
      (node (ref "RASPI") (pin "40") (pinfunction "40_40") (pintype "passive"))
    )
    (net (code "77") (name "unconnected-(U$1-5.5V-Pad5V)") (class "Default")
      (node (ref "U$1") (pin "5V") (pinfunction "5.5V_5V") (pintype "bidirectional"))
    )
    (net (code "78") (name "unconnected-(U$1-Pad3.3V)") (class "Default")
      (node (ref "U$1") (pin "3.3V") (pinfunction "3.3V_3.3V") (pintype "bidirectional"))
    )
    (net (code "79") (name "unconnected-(U$1-PadICSP1)") (class "Default")
      (node (ref "U$1") (pin "ICSP1") (pinfunction "ICSP1_ICSP1") (pintype "bidirectional"))
    )
    (net (code "80") (name "unconnected-(U$1-PadICSP2)") (class "Default")
      (node (ref "U$1") (pin "ICSP2") (pinfunction "ICSP2_ICSP2") (pintype "bidirectional"))
    )
    (net (code "81") (name "unconnected-(U$1-PadICSP3)") (class "Default")
      (node (ref "U$1") (pin "ICSP3") (pinfunction "ICSP3_ICSP3") (pintype "bidirectional"))
    )
    (net (code "82") (name "unconnected-(U$1-PadICSP4)") (class "Default")
      (node (ref "U$1") (pin "ICSP4") (pinfunction "ICSP4_ICSP4") (pintype "bidirectional"))
    )
    (net (code "83") (name "unconnected-(U$1-PadICSP5)") (class "Default")
      (node (ref "U$1") (pin "ICSP5") (pinfunction "ICSP5_ICSP5") (pintype "bidirectional"))
    )
    (net (code "84") (name "unconnected-(U$1-PadICSP6)") (class "Default")
      (node (ref "U$1") (pin "ICSP6") (pinfunction "ICSP6_ICSP6") (pintype "bidirectional"))
    )
    (net (code "85") (name "unconnected-(U$1-PadRST1)") (class "Default")
      (node (ref "U$1") (pin "RST1") (pinfunction "RST1_RST1") (pintype "bidirectional"))
    )
  )
)
